# schematic.net
KiCad netlist of a schematic drawn in EasyEDA
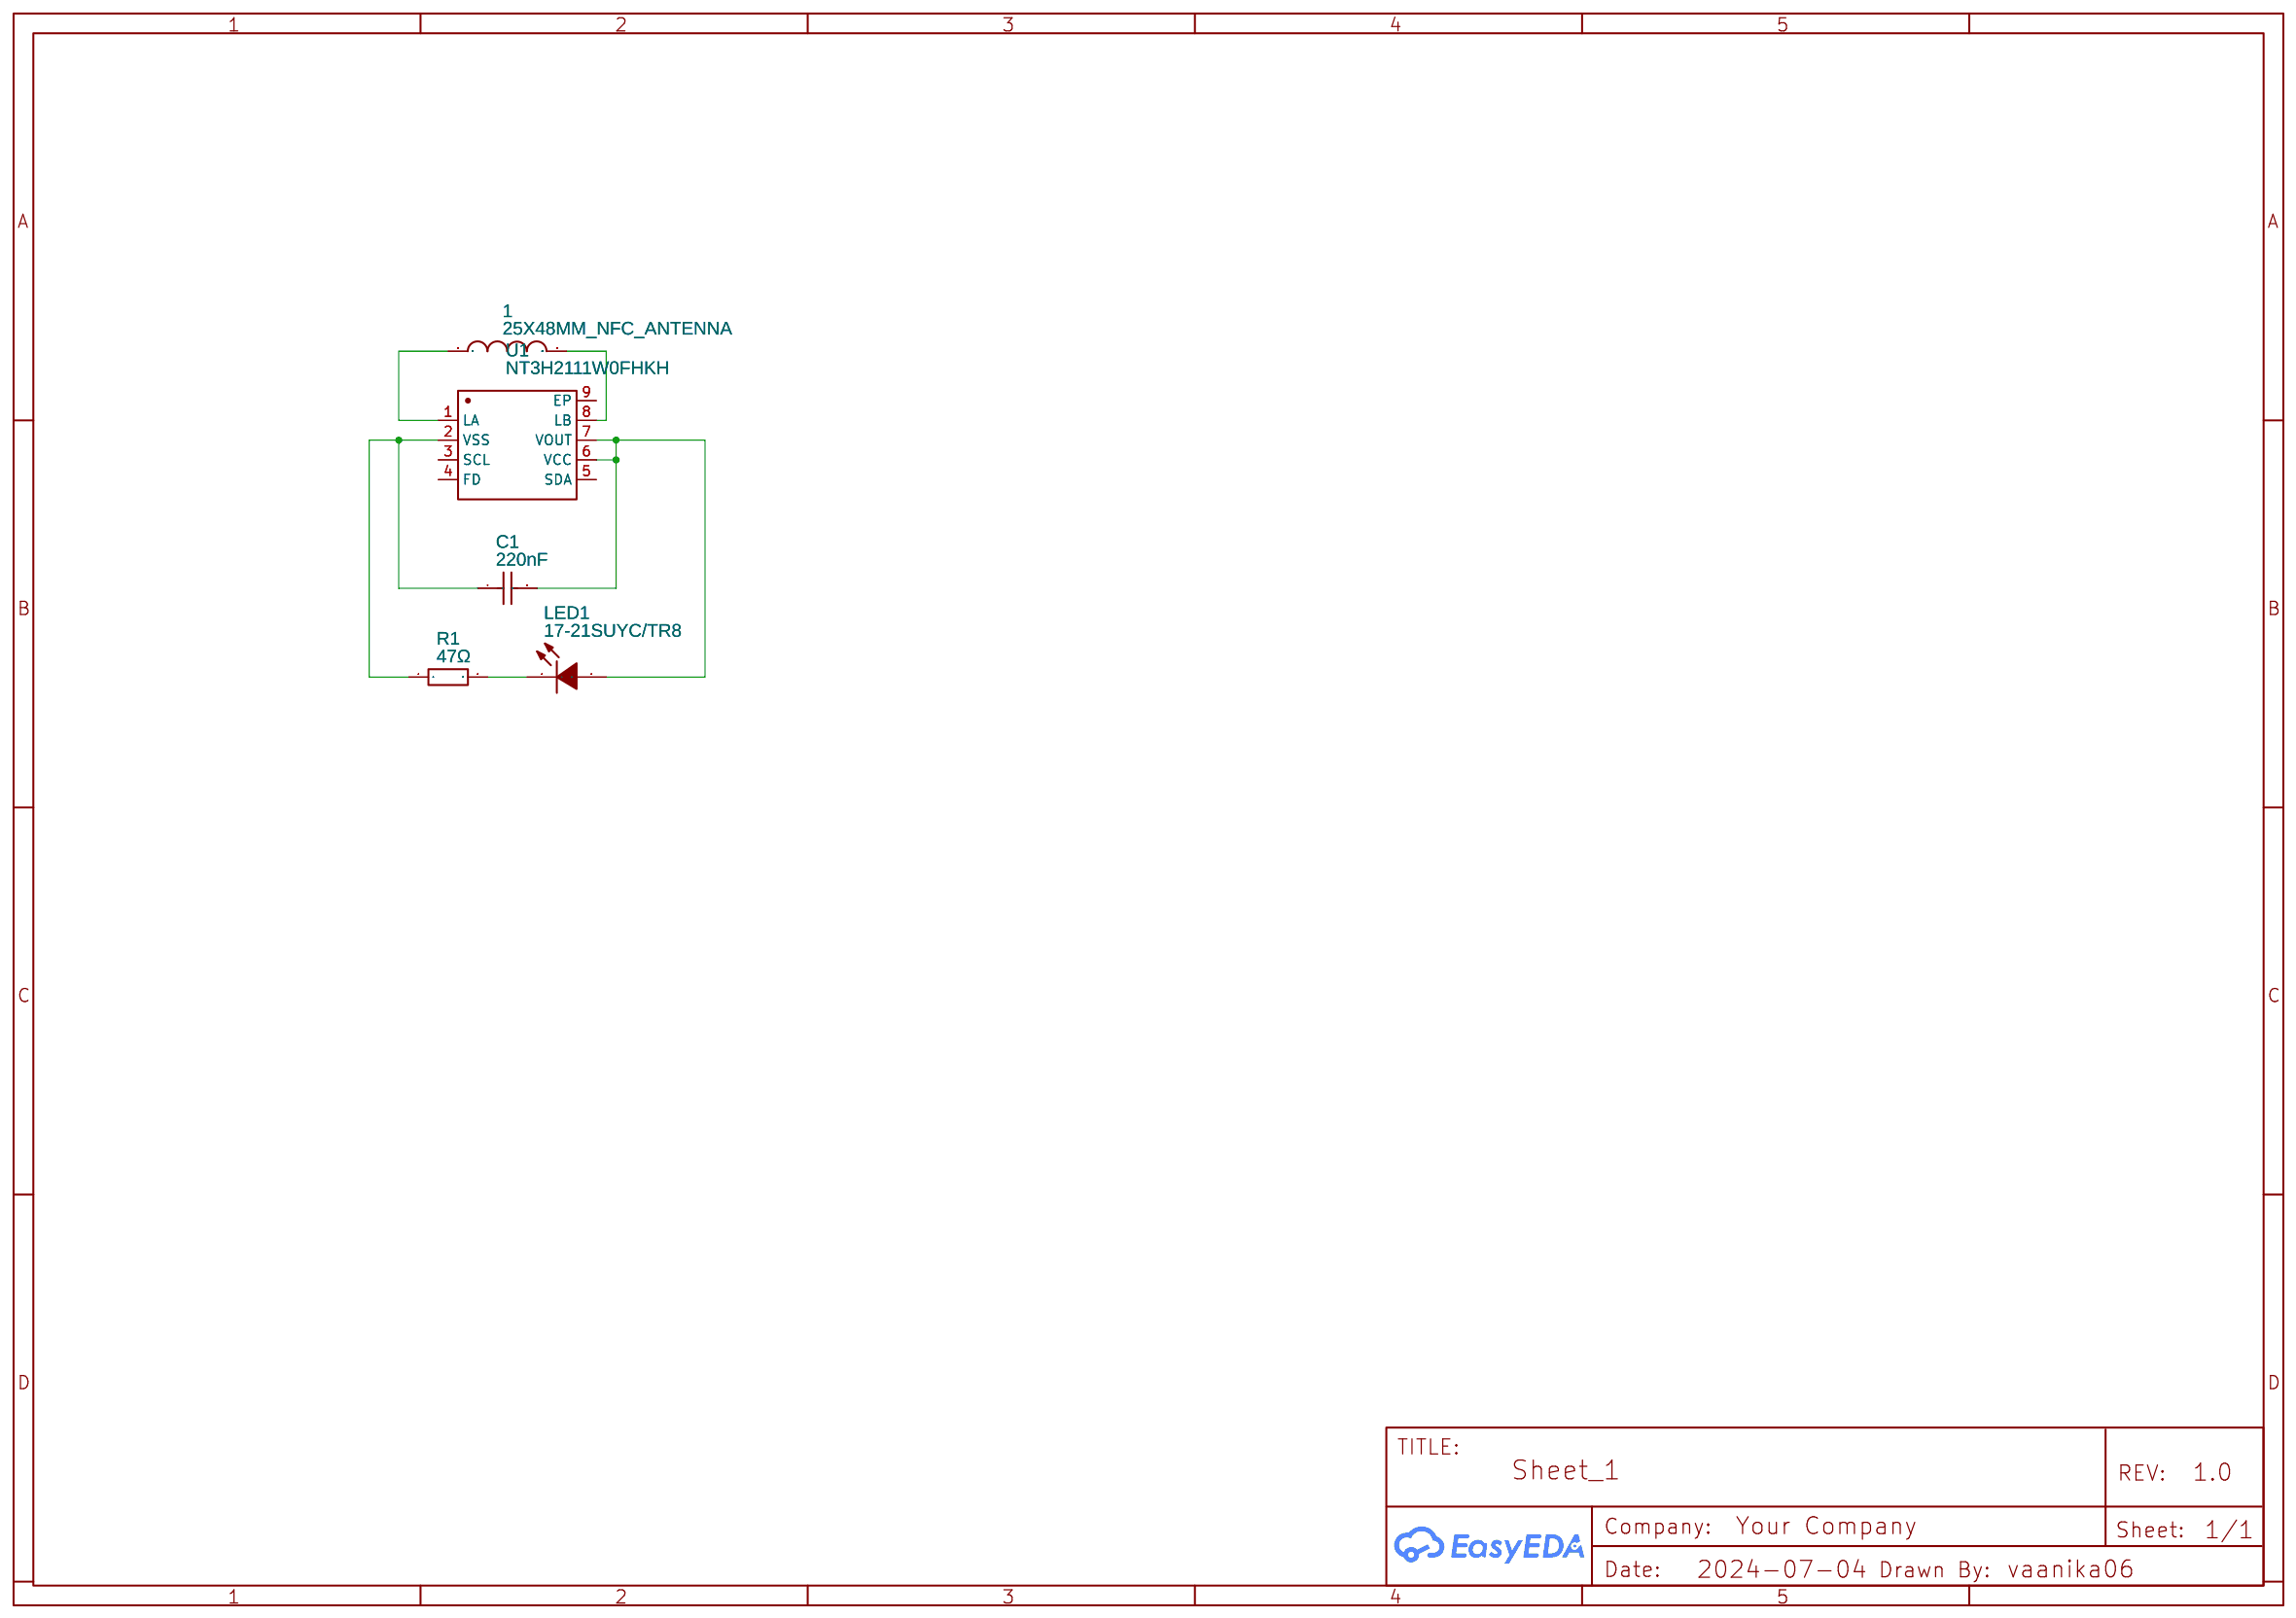
[diagram p0: schematic sheet]

(export (version "E")
  (design (tool "Eeschema 10.0.6"))
  (components
    (comp (ref "1") (value "25X48MM_NFC_ANTENNA") (libsource (lib "") (part "25X48MM_NFC_ANTENNA")))
    (comp (ref "C1")
      (value "220nF")
      (fields
        (field (name "Manufacturer Part") "CL10B224KA8NNNC")
        (field (name "Manufacturer") "SAMSUNG(三星)")
      )
      (libsource (lib "") (part "CL10B224KA8NNNC"))
    )
    (comp (ref "LED1")
      (value "17-21SUYC/TR8")
      (fields (field (name "Manufacturer Part") "KT-0805黄灯") (field (name "Manufacturer") "KENTO"))
      (libsource (lib "") (part "17-21SUYC/TR8"))
    )
    (comp (ref "R1")
      (value "47Ω")
      (fields
        (field (name "Manufacturer Part") "0603WAF470JT5E")
        (field (name "Manufacturer") "UNI-ROYAL(厚声)")
      )
      (libsource (lib "") (part "0603WAF470JT5E"))
    )
    (comp (ref "U1")
      (value "NT3H2111W0FHKH")
      (fields (field (name "Manufacturer") "NXP(恩智浦)"))
      (libsource (lib "") (part "NT3H2111W0FHKH"))
    )
  )
  (nets
    (net (code "1") (name "Net-(LED1-+)") (class "Default")
      (node (ref "C1") (pin "2") (pinfunction "2_2") (pintype "input"))
      (node (ref "LED1") (pin "1") (pinfunction "+_1") (pintype "unspecified"))
      (node (ref "U1") (pin "6") (pinfunction "VCC_6") (pintype "unspecified"))
      (node (ref "U1") (pin "7") (pinfunction "VOUT_7") (pintype "unspecified"))
    )
    (net (code "2") (name "Net-(LED1--)") (class "Default")
      (node (ref "LED1") (pin "2") (pinfunction "-_2") (pintype "unspecified"))
      (node (ref "R1") (pin "2") (pinfunction "2_2") (pintype "input"))
    )
    (net (code "3") (name "Net-(U1-LA)") (class "Default")
      (node (ref "1") (pin "P$1") (pinfunction "P$1_P$1") (pintype "bidirectional"))
      (node (ref "U1") (pin "1") (pinfunction "LA_1") (pintype "unspecified"))
    )
    (net (code "4") (name "Net-(U1-LB)") (class "Default")
      (node (ref "1") (pin "P$2") (pinfunction "P$2_P$2") (pintype "bidirectional"))
      (node (ref "U1") (pin "8") (pinfunction "LB_8") (pintype "unspecified"))
    )
    (net (code "5") (name "Net-(U1-VSS)") (class "Default")
      (node (ref "C1") (pin "1") (pinfunction "1_1") (pintype "input"))
      (node (ref "R1") (pin "1") (pinfunction "1_1") (pintype "input"))
      (node (ref "U1") (pin "2") (pinfunction "VSS_2") (pintype "unspecified"))
    )
    (net (code "6") (name "unconnected-(U1-EP-Pad9)") (class "Default")
      (node (ref "U1") (pin "9") (pinfunction "EP_9") (pintype "unspecified"))
    )
    (net (code "7") (name "unconnected-(U1-FD-Pad4)") (class "Default")
      (node (ref "U1") (pin "4") (pinfunction "FD_4") (pintype "unspecified"))
    )
    (net (code "8") (name "unconnected-(U1-SCL-Pad3)") (class "Default")
      (node (ref "U1") (pin "3") (pinfunction "SCL_3") (pintype "unspecified"))
    )
    (net (code "9") (name "unconnected-(U1-SDA-Pad5)") (class "Default")
      (node (ref "U1") (pin "5") (pinfunction "SDA_5") (pintype "unspecified"))
    )
  )
)
